# LITO.net
KiCad netlist of a schematic drawn in EasyEDA Pro
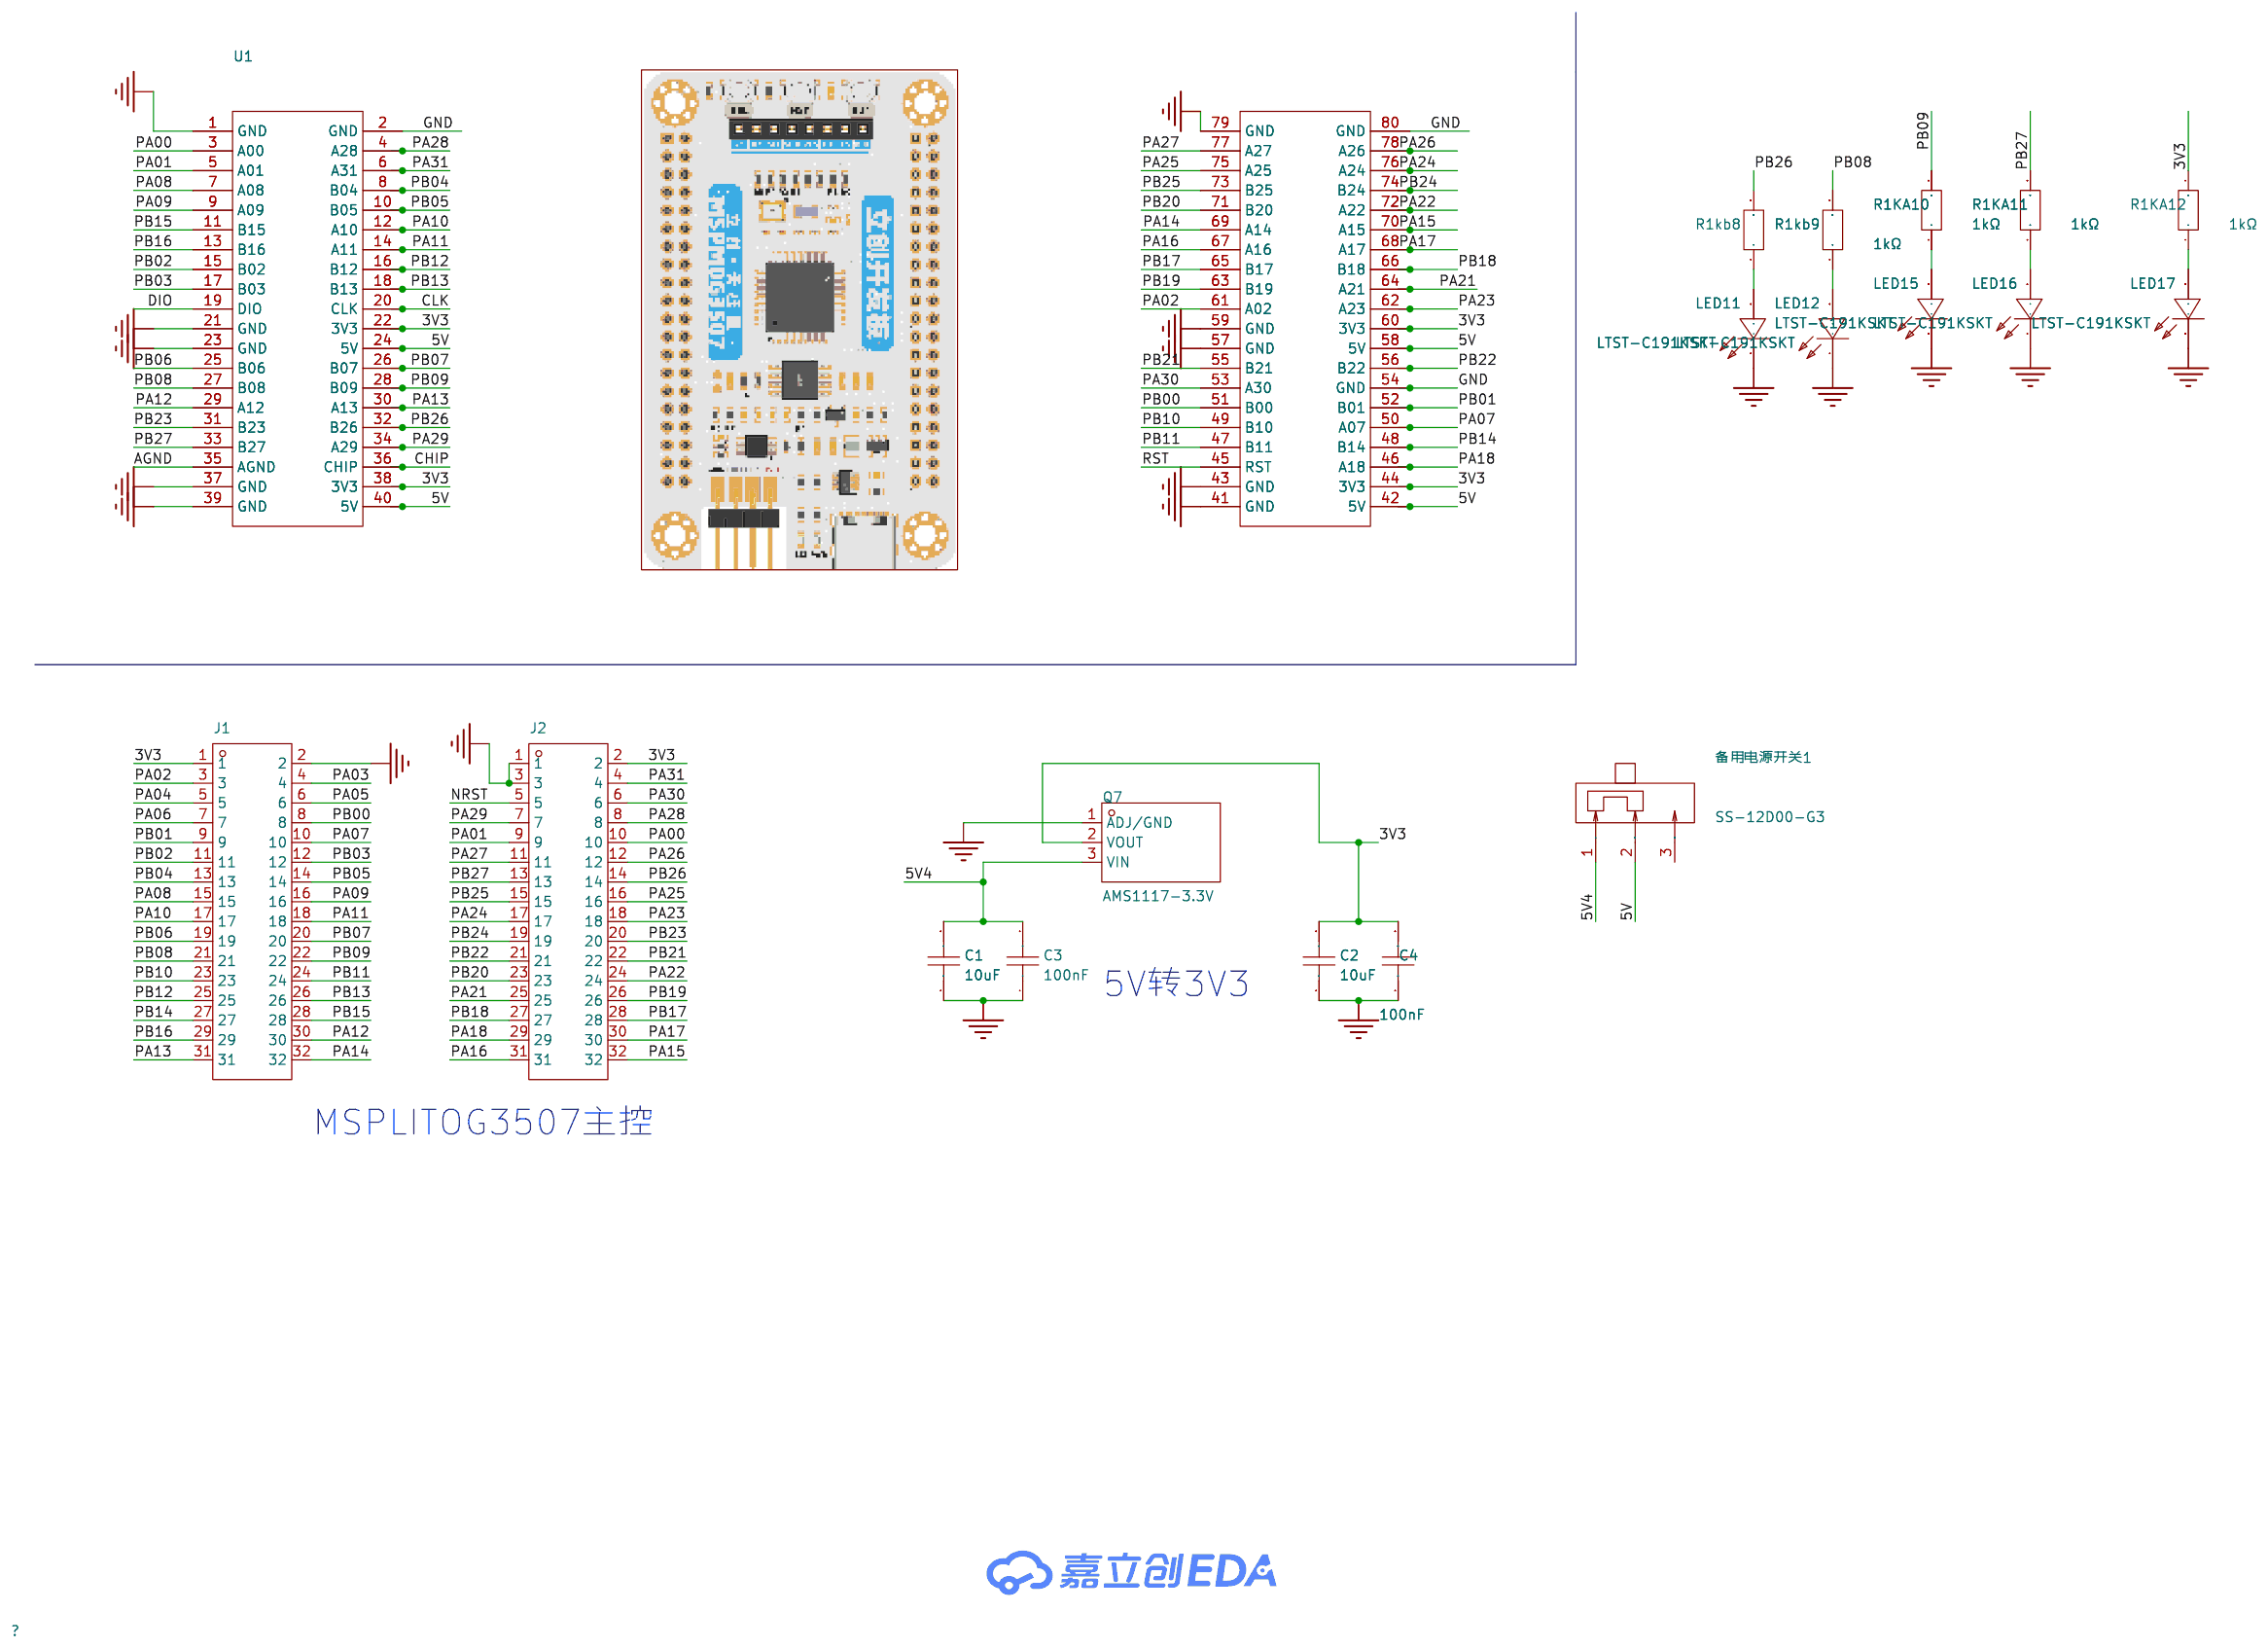
[diagram p0: schematic sheet]

(export (version "E")
  (design (tool "Eeschema 10.0.6"))
  (components
    (comp (ref "C1")
      (value "10uF")
      (footprint "easyedapro:C0805")
      (description "容值:10uF;精度:±10%;额定电压:25V;温度系数:X5R;")
      (fields
        (field (name "Manufacturer Part") "CGA0805X5R106K250MT")
        (field (name "Manufacturer") "HRE(芯声)")
      )
      (libsource (lib "easyedapro") (part "CGA0805X5R106K250MT"))
    )
    (comp (ref "C2")
      (value "10uF")
      (footprint "easyedapro:C0805")
      (description "容值:10uF;精度:±10%;额定电压:25V;温度系数:X5R;")
      (fields
        (field (name "Manufacturer Part") "CGA0805X5R106K250MT")
        (field (name "Manufacturer") "HRE(芯声)")
      )
      (libsource (lib "easyedapro") (part "CGA0805X5R106K250MT"))
    )
    (comp (ref "C3")
      (value "100nF")
      (footprint "easyedapro:C0603")
      (description "容值:100nF;精度:±10%;额定电压:50V;温度系数:X7R;")
      (fields
        (field (name "Manufacturer Part") "CGA0603X7R104K500JT")
        (field (name "Manufacturer") "HRE(芯声)")
      )
      (libsource (lib "easyedapro") (part "CGA0603X7R104K500JT"))
    )
    (comp (ref "C4")
      (value "100nF")
      (footprint "easyedapro:C0603")
      (description "容值:100nF;精度:±10%;额定电压:50V;温度系数:X7R;")
      (fields
        (field (name "Manufacturer Part") "CGA0603X7R104K500JT")
        (field (name "Manufacturer") "HRE(芯声)")
      )
      (libsource (lib "easyedapro") (part "CGA0603X7R104K500JT"))
    )
    (comp (ref "J1")
      (value "X6521FV-2x16-C85D32")
      (footprint "easyedapro:HDR-TH_32P-P2.54-V-F-R2-C16-S2.54")
      (fields (field (name "Manufacturer") "XKB Connection(中国星坤)"))
      (libsource (lib "easyedapro") (part "X6521FV-2X16-C85D32"))
    )
    (comp (ref "J2")
      (value "X6521FV-2x16-C85D32")
      (footprint "easyedapro:HDR-TH_32P-P2.54-V-F-R2-C16-S2.54")
      (fields (field (name "Manufacturer") "XKB Connection(中国星坤)"))
      (libsource (lib "easyedapro") (part "X6521FV-2X16-C85D32"))
    )
    (comp (ref "LED11")
      (value "LTST-C191KSKT")
      (footprint "easyedapro:LED0603-RD-YELLOW")
      (fields (field (name "Manufacturer") "LITEON(光宝)"))
      (libsource (lib "easyedapro") (part "LTST-C191KSKT"))
    )
    (comp (ref "LED12")
      (value "LTST-C191KSKT")
      (footprint "easyedapro:LED0603-RD-YELLOW")
      (fields (field (name "Manufacturer") "LITEON(光宝)"))
      (libsource (lib "easyedapro") (part "LTST-C191KSKT"))
    )
    (comp (ref "LED15")
      (value "LTST-C191KSKT")
      (footprint "easyedapro:LED0603-RD-YELLOW")
      (fields (field (name "Manufacturer") "LITEON(光宝)"))
      (libsource (lib "easyedapro") (part "LTST-C191KSKT"))
    )
    (comp (ref "LED16")
      (value "LTST-C191KSKT")
      (footprint "easyedapro:LED0603-RD-YELLOW")
      (fields (field (name "Manufacturer") "LITEON(光宝)"))
      (libsource (lib "easyedapro") (part "LTST-C191KSKT"))
    )
    (comp (ref "LED17")
      (value "LTST-C191KSKT")
      (footprint "easyedapro:LED0603-RD-YELLOW")
      (fields (field (name "Manufacturer") "LITEON(光宝)"))
      (libsource (lib "easyedapro") (part "LTST-C191KSKT"))
    )
    (comp (ref "Q7")
      (value "AMS1117-3.3V")
      (footprint "easyedapro:SOT-89-3_L4.5-W2.5-P1.50-LS4.2-BR")
      (description "输出类型:固定;工作电压:18V;输出电压:3.3V;输出电流:1A;输出极性:正极;")
      (fields (field (name "Manufacturer") "MSKSEMI(美森科)"))
      (libsource (lib "easyedapro") (part "AMS1117-3.3V_C5120796"))
    )
    (comp (ref "R1KA10")
      (value "1kΩ")
      (footprint "easyedapro:R0603")
      (description "电阻类型:厚膜电阻;阻值:1kΩ;精度:±1%;功率:100mW;最大工作电压:75V;")
      (fields (field (name "Manufacturer Part") "FCR0603F1K") (field (name "Manufacturer") "VO(翔胜)"))
      (libsource (lib "easyedapro") (part "FCR0603F1K"))
    )
    (comp (ref "R1KA11")
      (value "1kΩ")
      (footprint "easyedapro:R0603")
      (description "电阻类型:厚膜电阻;阻值:1kΩ;精度:±1%;功率:100mW;最大工作电压:75V;")
      (fields (field (name "Manufacturer Part") "FCR0603F1K") (field (name "Manufacturer") "VO(翔胜)"))
      (libsource (lib "easyedapro") (part "FCR0603F1K"))
    )
    (comp (ref "R1KA12")
      (value "1kΩ")
      (footprint "easyedapro:R0603")
      (description "电阻类型:厚膜电阻;阻值:1kΩ;精度:±1%;功率:100mW;最大工作电压:75V;")
      (fields (field (name "Manufacturer Part") "FCR0603F1K") (field (name "Manufacturer") "VO(翔胜)"))
      (libsource (lib "easyedapro") (part "FCR0603F1K"))
    )
    (comp (ref "R1kb8")
      (value "1kΩ")
      (footprint "easyedapro:R0603")
      (description "电阻类型:厚膜电阻;阻值:1kΩ;精度:±1%;功率:100mW;最大工作电压:75V;")
      (fields (field (name "Manufacturer Part") "FCR0603F1K") (field (name "Manufacturer") "VO(翔胜)"))
      (libsource (lib "easyedapro") (part "FCR0603F1K"))
    )
    (comp (ref "R1kb9")
      (value "1kΩ")
      (footprint "easyedapro:R0603")
      (description "电阻类型:厚膜电阻;阻值:1kΩ;精度:±1%;功率:100mW;最大工作电压:75V;")
      (fields (field (name "Manufacturer Part") "FCR0603F1K") (field (name "Manufacturer") "VO(翔胜)"))
      (libsource (lib "easyedapro") (part "FCR0603F1K"))
    )
    (comp (ref "U1")
      (value "LCKFB-TMX-MSPM0G3507")
      (footprint "easyedapro:COMM-TH_LCKFB-TMX-MSPM0G3507")
      (fields (field (name "Manufacturer") "立创开发板"))
      (libsource (lib "easyedapro") (part "LCKFB-TMX-MSPM0G3507"))
    )
    (comp (ref "备用电源开关1")
      (value "SS-12D00-G3")
      (footprint "easyedapro:SW-TH_3P-L8.8-W3.9-P2.50_SS12D00G3")
      (description "操作正拨 插件立式 尺寸大型 两档位")
      (fields (field (name "Manufacturer") "SOFNG(硕方)"))
      (libsource (lib "easyedapro") (part "SS-12D00-G3"))
    )
  )
  (nets
    (net (code "1") (name "/3V3") (class "Default")
      (node (ref "C2") (pin "2") (pinfunction "2_2") (pintype "unspecified"))
      (node (ref "C4") (pin "2") (pinfunction "2_2") (pintype "unspecified"))
      (node (ref "J1") (pin "1") (pinfunction "1_1") (pintype "unspecified"))
      (node (ref "J2") (pin "2") (pinfunction "2_2") (pintype "unspecified"))
      (node (ref "Q7") (pin "2") (pinfunction "VOUT_2") (pintype "unspecified"))
      (node (ref "R1KA12") (pin "2") (pinfunction "2_2") (pintype "unspecified"))
      (node (ref "U1") (pin "22") (pinfunction "3V3_22") (pintype "unspecified"))
      (node (ref "U1") (pin "38") (pinfunction "3V3_38") (pintype "unspecified"))
      (node (ref "U1") (pin "44") (pinfunction "3V3_44") (pintype "unspecified"))
      (node (ref "U1") (pin "60") (pinfunction "3V3_60") (pintype "unspecified"))
    )
    (net (code "2") (name "/5V") (class "Default")
      (node (ref "U1") (pin "24") (pinfunction "5V_24") (pintype "unspecified"))
      (node (ref "U1") (pin "40") (pinfunction "5V_40") (pintype "unspecified"))
      (node (ref "U1") (pin "42") (pinfunction "5V_42") (pintype "unspecified"))
      (node (ref "U1") (pin "58") (pinfunction "5V_58") (pintype "unspecified"))
      (node (ref "备用电源开关1") (pin "2") (pinfunction "2_2") (pintype "unspecified"))
    )
    (net (code "3") (name "/5V4") (class "Default")
      (node (ref "C1") (pin "2") (pinfunction "2_2") (pintype "unspecified"))
      (node (ref "C3") (pin "2") (pinfunction "2_2") (pintype "unspecified"))
      (node (ref "Q7") (pin "3") (pinfunction "VIN_3") (pintype "unspecified"))
      (node (ref "备用电源开关1") (pin "1") (pinfunction "1_1") (pintype "unspecified"))
    )
    (net (code "4") (name "/AGND") (class "Default")
      (node (ref "U1") (pin "35") (pinfunction "AGND_35") (pintype "unspecified"))
    )
    (net (code "5") (name "/CHIP") (class "Default")
      (node (ref "U1") (pin "36") (pinfunction "CHIP_36") (pintype "unspecified"))
    )
    (net (code "6") (name "/CLK") (class "Default")
      (node (ref "U1") (pin "20") (pinfunction "CLK_20") (pintype "unspecified"))
    )
    (net (code "7") (name "/DIO") (class "Default")
      (node (ref "U1") (pin "19") (pinfunction "DIO_19") (pintype "unspecified"))
    )
    (net (code "8") (name "/NRST") (class "Default")
      (node (ref "J2") (pin "5") (pinfunction "5_5") (pintype "unspecified"))
    )
    (net (code "9") (name "/PA00") (class "Default")
      (node (ref "J2") (pin "10") (pinfunction "10_10") (pintype "unspecified"))
      (node (ref "U1") (pin "3") (pinfunction "A00_3") (pintype "bidirectional"))
    )
    (net (code "10") (name "/PA01") (class "Default")
      (node (ref "J2") (pin "9") (pinfunction "9_9") (pintype "unspecified"))
      (node (ref "U1") (pin "5") (pinfunction "A01_5") (pintype "unspecified"))
    )
    (net (code "11") (name "/PA02") (class "Default")
      (node (ref "J1") (pin "3") (pinfunction "3_3") (pintype "unspecified"))
      (node (ref "U1") (pin "61") (pinfunction "A02_61") (pintype "unspecified"))
    )
    (net (code "12") (name "/PA03") (class "Default")
      (node (ref "J1") (pin "4") (pinfunction "4_4") (pintype "unspecified"))
    )
    (net (code "13") (name "/PA04") (class "Default")
      (node (ref "J1") (pin "5") (pinfunction "5_5") (pintype "unspecified"))
    )
    (net (code "14") (name "/PA05") (class "Default")
      (node (ref "J1") (pin "6") (pinfunction "6_6") (pintype "unspecified"))
    )
    (net (code "15") (name "/PA06") (class "Default")
      (node (ref "J1") (pin "7") (pinfunction "7_7") (pintype "unspecified"))
    )
    (net (code "16") (name "/PA07") (class "Default")
      (node (ref "J1") (pin "10") (pinfunction "10_10") (pintype "unspecified"))
      (node (ref "U1") (pin "50") (pinfunction "A07_50") (pintype "unspecified"))
    )
    (net (code "17") (name "/PA08") (class "Default")
      (node (ref "J1") (pin "15") (pinfunction "15_15") (pintype "unspecified"))
      (node (ref "U1") (pin "7") (pinfunction "A08_7") (pintype "unspecified"))
    )
    (net (code "18") (name "/PA09") (class "Default")
      (node (ref "J1") (pin "16") (pinfunction "16_16") (pintype "unspecified"))
      (node (ref "U1") (pin "9") (pinfunction "A09_9") (pintype "unspecified"))
    )
    (net (code "19") (name "/PA10") (class "Default")
      (node (ref "J1") (pin "17") (pinfunction "17_17") (pintype "unspecified"))
      (node (ref "U1") (pin "12") (pinfunction "A10_12") (pintype "unspecified"))
    )
    (net (code "20") (name "/PA11") (class "Default")
      (node (ref "J1") (pin "18") (pinfunction "18_18") (pintype "unspecified"))
      (node (ref "U1") (pin "14") (pinfunction "A11_14") (pintype "unspecified"))
    )
    (net (code "21") (name "/PA12") (class "Default")
      (node (ref "J1") (pin "30") (pinfunction "30_30") (pintype "unspecified"))
      (node (ref "U1") (pin "29") (pinfunction "A12_29") (pintype "unspecified"))
    )
    (net (code "22") (name "/PA13") (class "Default")
      (node (ref "J1") (pin "31") (pinfunction "31_31") (pintype "unspecified"))
      (node (ref "U1") (pin "30") (pinfunction "A13_30") (pintype "unspecified"))
    )
    (net (code "23") (name "/PA14") (class "Default")
      (node (ref "J1") (pin "32") (pinfunction "32_32") (pintype "unspecified"))
      (node (ref "U1") (pin "69") (pinfunction "A14_69") (pintype "unspecified"))
    )
    (net (code "24") (name "/PA15") (class "Default")
      (node (ref "J2") (pin "32") (pinfunction "32_32") (pintype "unspecified"))
      (node (ref "U1") (pin "70") (pinfunction "A15_70") (pintype "unspecified"))
    )
    (net (code "25") (name "/PA16") (class "Default")
      (node (ref "J2") (pin "31") (pinfunction "31_31") (pintype "unspecified"))
      (node (ref "U1") (pin "67") (pinfunction "A16_67") (pintype "unspecified"))
    )
    (net (code "26") (name "/PA17") (class "Default")
      (node (ref "J2") (pin "30") (pinfunction "30_30") (pintype "unspecified"))
      (node (ref "U1") (pin "68") (pinfunction "A17_68") (pintype "unspecified"))
    )
    (net (code "27") (name "/PA18") (class "Default")
      (node (ref "J2") (pin "29") (pinfunction "29_29") (pintype "unspecified"))
      (node (ref "U1") (pin "46") (pinfunction "A18_46") (pintype "unspecified"))
    )
    (net (code "28") (name "/PA21") (class "Default")
      (node (ref "J2") (pin "25") (pinfunction "25_25") (pintype "unspecified"))
      (node (ref "U1") (pin "64") (pinfunction "A21_64") (pintype "unspecified"))
    )
    (net (code "29") (name "/PA22") (class "Default")
      (node (ref "J2") (pin "24") (pinfunction "24_24") (pintype "unspecified"))
      (node (ref "U1") (pin "72") (pinfunction "A22_72") (pintype "unspecified"))
    )
    (net (code "30") (name "/PA23") (class "Default")
      (node (ref "J2") (pin "18") (pinfunction "18_18") (pintype "unspecified"))
      (node (ref "U1") (pin "62") (pinfunction "A23_62") (pintype "unspecified"))
    )
    (net (code "31") (name "/PA24") (class "Default")
      (node (ref "J2") (pin "17") (pinfunction "17_17") (pintype "unspecified"))
      (node (ref "U1") (pin "76") (pinfunction "A24_76") (pintype "unspecified"))
    )
    (net (code "32") (name "/PA25") (class "Default")
      (node (ref "J2") (pin "16") (pinfunction "16_16") (pintype "unspecified"))
      (node (ref "U1") (pin "75") (pinfunction "A25_75") (pintype "unspecified"))
    )
    (net (code "33") (name "/PA26") (class "Default")
      (node (ref "J2") (pin "12") (pinfunction "12_12") (pintype "unspecified"))
      (node (ref "U1") (pin "78") (pinfunction "A26_78") (pintype "unspecified"))
    )
    (net (code "34") (name "/PA27") (class "Default")
      (node (ref "J2") (pin "11") (pinfunction "11_11") (pintype "unspecified"))
      (node (ref "U1") (pin "77") (pinfunction "A27_77") (pintype "bidirectional"))
    )
    (net (code "35") (name "/PA28") (class "Default")
      (node (ref "J2") (pin "8") (pinfunction "8_8") (pintype "unspecified"))
      (node (ref "U1") (pin "4") (pinfunction "A28_4") (pintype "unspecified"))
    )
    (net (code "36") (name "/PA29") (class "Default")
      (node (ref "J2") (pin "7") (pinfunction "7_7") (pintype "unspecified"))
      (node (ref "U1") (pin "34") (pinfunction "A29_34") (pintype "unspecified"))
    )
    (net (code "37") (name "/PA30") (class "Default")
      (node (ref "J2") (pin "6") (pinfunction "6_6") (pintype "unspecified"))
      (node (ref "U1") (pin "53") (pinfunction "A30_53") (pintype "unspecified"))
    )
    (net (code "38") (name "/PA31") (class "Default")
      (node (ref "J2") (pin "4") (pinfunction "4_4") (pintype "unspecified"))
      (node (ref "U1") (pin "6") (pinfunction "A31_6") (pintype "unspecified"))
    )
    (net (code "39") (name "/PB00") (class "Default")
      (node (ref "J1") (pin "8") (pinfunction "8_8") (pintype "unspecified"))
      (node (ref "U1") (pin "51") (pinfunction "B00_51") (pintype "unspecified"))
    )
    (net (code "40") (name "/PB01") (class "Default")
      (node (ref "J1") (pin "9") (pinfunction "9_9") (pintype "unspecified"))
      (node (ref "U1") (pin "52") (pinfunction "B01_52") (pintype "unspecified"))
    )
    (net (code "41") (name "/PB02") (class "Default")
      (node (ref "J1") (pin "11") (pinfunction "11_11") (pintype "unspecified"))
      (node (ref "U1") (pin "15") (pinfunction "B02_15") (pintype "unspecified"))
    )
    (net (code "42") (name "/PB03") (class "Default")
      (node (ref "J1") (pin "12") (pinfunction "12_12") (pintype "unspecified"))
      (node (ref "U1") (pin "17") (pinfunction "B03_17") (pintype "unspecified"))
    )
    (net (code "43") (name "/PB04") (class "Default")
      (node (ref "J1") (pin "13") (pinfunction "13_13") (pintype "unspecified"))
      (node (ref "U1") (pin "8") (pinfunction "B04_8") (pintype "unspecified"))
    )
    (net (code "44") (name "/PB05") (class "Default")
      (node (ref "J1") (pin "14") (pinfunction "14_14") (pintype "unspecified"))
      (node (ref "U1") (pin "10") (pinfunction "B05_10") (pintype "unspecified"))
    )
    (net (code "45") (name "/PB06") (class "Default")
      (node (ref "J1") (pin "19") (pinfunction "19_19") (pintype "unspecified"))
      (node (ref "U1") (pin "25") (pinfunction "B06_25") (pintype "unspecified"))
    )
    (net (code "46") (name "/PB07") (class "Default")
      (node (ref "J1") (pin "20") (pinfunction "20_20") (pintype "unspecified"))
      (node (ref "U1") (pin "26") (pinfunction "B07_26") (pintype "unspecified"))
    )
    (net (code "47") (name "/PB08") (class "Default")
      (node (ref "J1") (pin "21") (pinfunction "21_21") (pintype "unspecified"))
      (node (ref "R1kb9") (pin "2") (pinfunction "2_2") (pintype "unspecified"))
      (node (ref "U1") (pin "27") (pinfunction "B08_27") (pintype "unspecified"))
    )
    (net (code "48") (name "/PB09") (class "Default")
      (node (ref "J1") (pin "22") (pinfunction "22_22") (pintype "unspecified"))
      (node (ref "R1KA10") (pin "2") (pinfunction "2_2") (pintype "unspecified"))
      (node (ref "U1") (pin "28") (pinfunction "B09_28") (pintype "unspecified"))
    )
    (net (code "49") (name "/PB10") (class "Default")
      (node (ref "J1") (pin "23") (pinfunction "23_23") (pintype "unspecified"))
      (node (ref "U1") (pin "49") (pinfunction "B10_49") (pintype "unspecified"))
    )
    (net (code "50") (name "/PB11") (class "Default")
      (node (ref "J1") (pin "24") (pinfunction "24_24") (pintype "unspecified"))
      (node (ref "U1") (pin "47") (pinfunction "B11_47") (pintype "unspecified"))
    )
    (net (code "51") (name "/PB12") (class "Default")
      (node (ref "J1") (pin "25") (pinfunction "25_25") (pintype "unspecified"))
      (node (ref "U1") (pin "16") (pinfunction "B12_16") (pintype "unspecified"))
    )
    (net (code "52") (name "/PB13") (class "Default")
      (node (ref "J1") (pin "26") (pinfunction "26_26") (pintype "unspecified"))
      (node (ref "U1") (pin "18") (pinfunction "B13_18") (pintype "unspecified"))
    )
    (net (code "53") (name "/PB14") (class "Default")
      (node (ref "J1") (pin "27") (pinfunction "27_27") (pintype "unspecified"))
      (node (ref "U1") (pin "48") (pinfunction "B14_48") (pintype "unspecified"))
    )
    (net (code "54") (name "/PB15") (class "Default")
      (node (ref "J1") (pin "28") (pinfunction "28_28") (pintype "unspecified"))
      (node (ref "U1") (pin "11") (pinfunction "B15_11") (pintype "unspecified"))
    )
    (net (code "55") (name "/PB16") (class "Default")
      (node (ref "J1") (pin "29") (pinfunction "29_29") (pintype "unspecified"))
      (node (ref "U1") (pin "13") (pinfunction "B16_13") (pintype "unspecified"))
    )
    (net (code "56") (name "/PB17") (class "Default")
      (node (ref "J2") (pin "28") (pinfunction "28_28") (pintype "unspecified"))
      (node (ref "U1") (pin "65") (pinfunction "B17_65") (pintype "unspecified"))
    )
    (net (code "57") (name "/PB18") (class "Default")
      (node (ref "J2") (pin "27") (pinfunction "27_27") (pintype "unspecified"))
      (node (ref "U1") (pin "66") (pinfunction "B18_66") (pintype "unspecified"))
    )
    (net (code "58") (name "/PB19") (class "Default")
      (node (ref "J2") (pin "26") (pinfunction "26_26") (pintype "unspecified"))
      (node (ref "U1") (pin "63") (pinfunction "B19_63") (pintype "unspecified"))
    )
    (net (code "59") (name "/PB20") (class "Default")
      (node (ref "J2") (pin "23") (pinfunction "23_23") (pintype "unspecified"))
      (node (ref "U1") (pin "71") (pinfunction "B20_71") (pintype "unspecified"))
    )
    (net (code "60") (name "/PB21") (class "Default")
      (node (ref "J2") (pin "22") (pinfunction "22_22") (pintype "unspecified"))
      (node (ref "U1") (pin "55") (pinfunction "B21_55") (pintype "unspecified"))
    )
    (net (code "61") (name "/PB22") (class "Default")
      (node (ref "J2") (pin "21") (pinfunction "21_21") (pintype "unspecified"))
      (node (ref "U1") (pin "56") (pinfunction "B22_56") (pintype "unspecified"))
    )
    (net (code "62") (name "/PB23") (class "Default")
      (node (ref "J2") (pin "20") (pinfunction "20_20") (pintype "unspecified"))
      (node (ref "U1") (pin "31") (pinfunction "B23_31") (pintype "unspecified"))
    )
    (net (code "63") (name "/PB24") (class "Default")
      (node (ref "J2") (pin "19") (pinfunction "19_19") (pintype "unspecified"))
      (node (ref "U1") (pin "74") (pinfunction "B24_74") (pintype "unspecified"))
    )
    (net (code "64") (name "/PB25") (class "Default")
      (node (ref "J2") (pin "15") (pinfunction "15_15") (pintype "unspecified"))
      (node (ref "U1") (pin "73") (pinfunction "B25_73") (pintype "unspecified"))
    )
    (net (code "65") (name "/PB26") (class "Default")
      (node (ref "J2") (pin "14") (pinfunction "14_14") (pintype "unspecified"))
      (node (ref "R1kb8") (pin "2") (pinfunction "2_2") (pintype "unspecified"))
      (node (ref "U1") (pin "32") (pinfunction "B26_32") (pintype "unspecified"))
    )
    (net (code "66") (name "/PB27") (class "Default")
      (node (ref "J2") (pin "13") (pinfunction "13_13") (pintype "unspecified"))
      (node (ref "R1KA11") (pin "2") (pinfunction "2_2") (pintype "unspecified"))
      (node (ref "U1") (pin "33") (pinfunction "B27_33") (pintype "unspecified"))
    )
    (net (code "67") (name "/RST") (class "Default")
      (node (ref "U1") (pin "45") (pinfunction "RST_45") (pintype "unspecified"))
    )
    (net (code "68") (name "GND") (class "Default")
      (node (ref "C1") (pin "1") (pinfunction "1_1") (pintype "unspecified"))
      (node (ref "C2") (pin "1") (pinfunction "1_1") (pintype "unspecified"))
      (node (ref "C3") (pin "1") (pinfunction "1_1") (pintype "unspecified"))
      (node (ref "C4") (pin "1") (pinfunction "1_1") (pintype "unspecified"))
      (node (ref "J1") (pin "2") (pinfunction "2_2") (pintype "unspecified"))
      (node (ref "J2") (pin "1") (pinfunction "1_1") (pintype "unspecified"))
      (node (ref "J2") (pin "3") (pinfunction "3_3") (pintype "unspecified"))
      (node (ref "LED11") (pin "1") (pinfunction "-_1") (pintype "unspecified"))
      (node (ref "LED12") (pin "1") (pinfunction "-_1") (pintype "unspecified"))
      (node (ref "LED15") (pin "1") (pinfunction "-_1") (pintype "unspecified"))
      (node (ref "LED16") (pin "1") (pinfunction "-_1") (pintype "unspecified"))
      (node (ref "LED17") (pin "1") (pinfunction "-_1") (pintype "unspecified"))
      (node (ref "Q7") (pin "1") (pinfunction "ADJ/GND_1") (pintype "unspecified"))
      (node (ref "U1") (pin "1") (pinfunction "GND_1") (pintype "unspecified"))
      (node (ref "U1") (pin "2") (pinfunction "GND_2") (pintype "unspecified"))
      (node (ref "U1") (pin "21") (pinfunction "GND_21") (pintype "unspecified"))
      (node (ref "U1") (pin "23") (pinfunction "GND_23") (pintype "unspecified"))
      (node (ref "U1") (pin "37") (pinfunction "GND_37") (pintype "unspecified"))
      (node (ref "U1") (pin "39") (pinfunction "GND_39") (pintype "unspecified"))
      (node (ref "U1") (pin "41") (pinfunction "GND_41") (pintype "unspecified"))
      (node (ref "U1") (pin "43") (pinfunction "GND_43") (pintype "unspecified"))
      (node (ref "U1") (pin "54") (pinfunction "GND_54") (pintype "unspecified"))
      (node (ref "U1") (pin "57") (pinfunction "GND_57") (pintype "unspecified"))
      (node (ref "U1") (pin "59") (pinfunction "GND_59") (pintype "unspecified"))
      (node (ref "U1") (pin "79") (pinfunction "GND_79") (pintype "unspecified"))
      (node (ref "U1") (pin "80") (pinfunction "GND_80") (pintype "unspecified"))
    )
    (net (code "69") (name "Net-(LED11-+)") (class "Default")
      (node (ref "LED11") (pin "2") (pinfunction "+_2") (pintype "unspecified"))
      (node (ref "R1kb8") (pin "1") (pinfunction "1_1") (pintype "unspecified"))
    )
    (net (code "70") (name "Net-(LED12-+)") (class "Default")
      (node (ref "LED12") (pin "2") (pinfunction "+_2") (pintype "unspecified"))
      (node (ref "R1kb9") (pin "1") (pinfunction "1_1") (pintype "unspecified"))
    )
    (net (code "71") (name "Net-(LED15-+)") (class "Default")
      (node (ref "LED15") (pin "2") (pinfunction "+_2") (pintype "unspecified"))
      (node (ref "R1KA10") (pin "1") (pinfunction "1_1") (pintype "unspecified"))
    )
    (net (code "72") (name "Net-(LED16-+)") (class "Default")
      (node (ref "LED16") (pin "2") (pinfunction "+_2") (pintype "unspecified"))
      (node (ref "R1KA11") (pin "1") (pinfunction "1_1") (pintype "unspecified"))
    )
    (net (code "73") (name "Net-(LED17-+)") (class "Default")
      (node (ref "LED17") (pin "2") (pinfunction "+_2") (pintype "unspecified"))
      (node (ref "R1KA12") (pin "1") (pinfunction "1_1") (pintype "unspecified"))
    )
    (net (code "74") (name "unconnected-(备用电源开关1-Pad3)") (class "Default")
      (node (ref "备用电源开关1") (pin "3") (pinfunction "3_3") (pintype "unspecified"))
    )
  )
)
